# MicroSpecSensorBoard_periphericDevices_V.net
KiCad netlist of a schematic drawn in Altium Designer
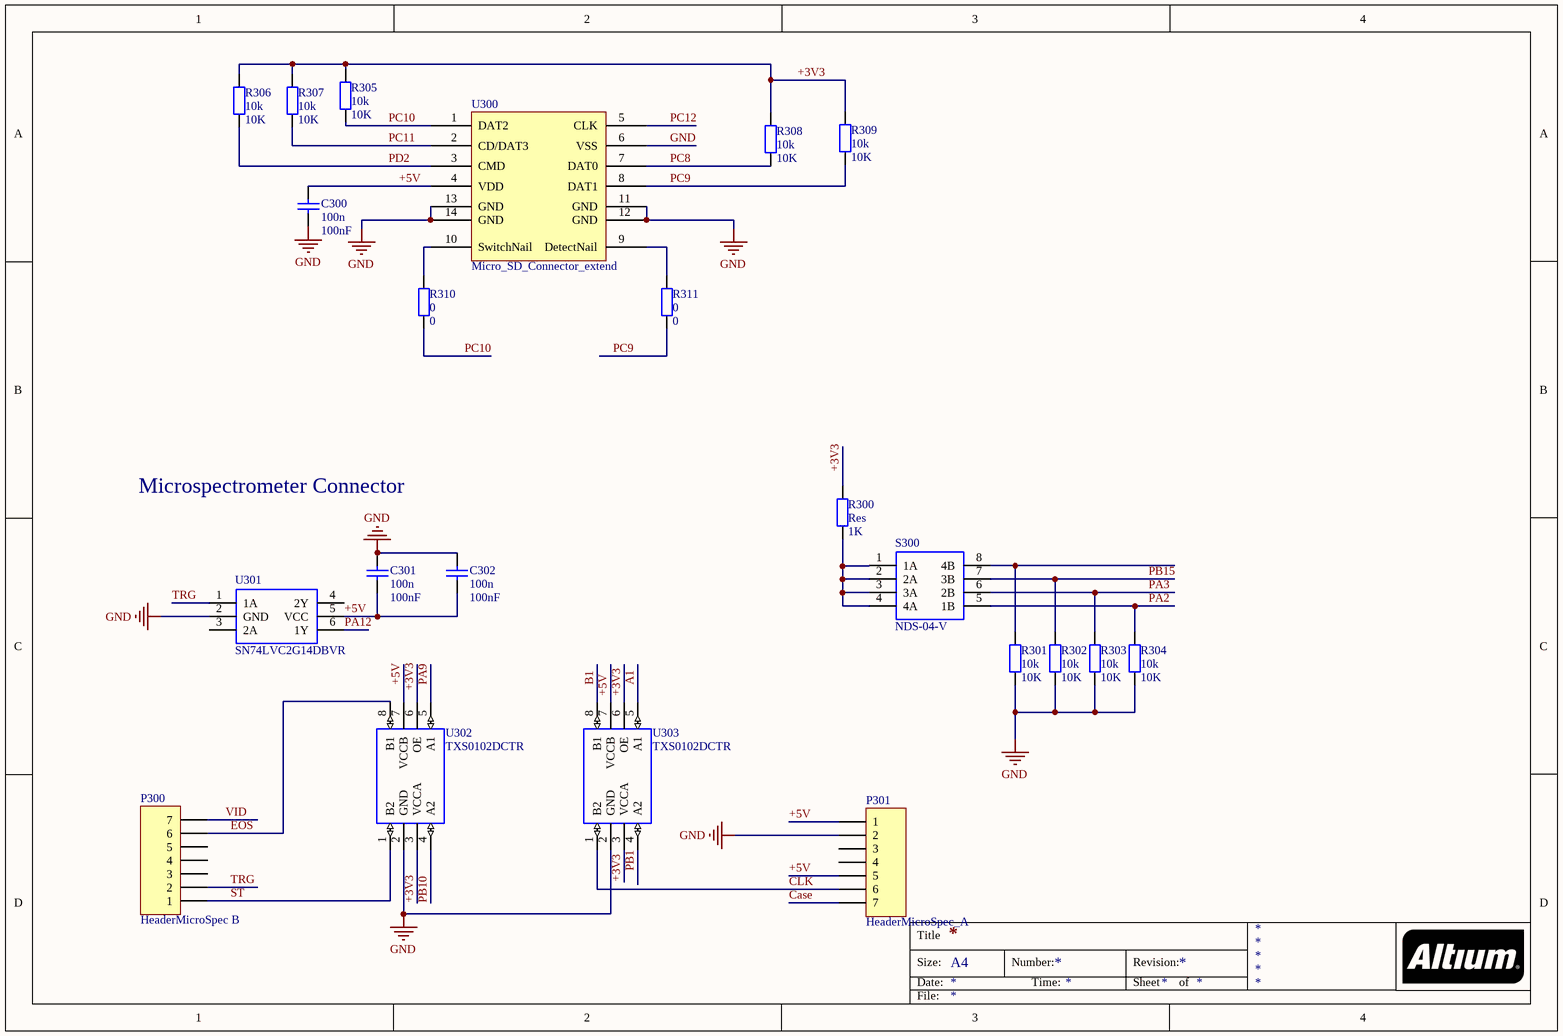
[diagram p0: MicroSpecSensorBoard_periphericDevices_V2_1.SchDoc]

(export (version "E")
  (design (tool "Eeschema 10.0.6"))
  (components
    (comp (ref "C300")
      (value "100n")
      (footprint "6-0805_L")
      (description "Capacitor")
      (fields (field (name "ALTIUM_VALUE") "100nF") (field (name "PUBLISHER") "Altium Limited"))
      (libsource (lib "USER_Library") (part "Cap"))
    )
    (comp (ref "C301")
      (value "100n")
      (footprint "6-0805_L")
      (description "Capacitor")
      (fields (field (name "ALTIUM_VALUE") "100nF") (field (name "PUBLISHER") "Altium Limited"))
      (libsource (lib "USER_Library") (part "Cap"))
    )
    (comp (ref "C302")
      (value "100n")
      (footprint "6-0805_L")
      (description "Capacitor")
      (fields (field (name "ALTIUM_VALUE") "100nF") (field (name "PUBLISHER") "Altium Limited"))
      (libsource (lib "USER_Library") (part "Cap"))
    )
    (comp (ref "P300")
      (value "HeaderMicroSpec B")
      (footprint "HDR1X7")
      (description "Header, 7-Pin")
      (fields (field (name "PUBLISHER") "Altium Limited"))
      (libsource (lib "Miscellaneous Connectors") (part "Header 7"))
    )
    (comp (ref "P301")
      (value "HeaderMicroSpec_A")
      (footprint "HDR1X7")
      (description "Header, 7-Pin")
      (fields (field (name "PUBLISHER") "Altium Limited"))
      (libsource (lib "") (part "Header 7_1"))
    )
    (comp (ref "R300")
      (value "Res")
      (footprint "6-0805_L")
      (description "Resistor")
      (fields (field (name "ALTIUM_VALUE") "1K") (field (name "PUBLISHER") "Altium Limited"))
      (libsource (lib "USER_Library") (part "Res2"))
    )
    (comp (ref "R301")
      (value "10k")
      (footprint "6-0805_L")
      (description "Resistor")
      (fields (field (name "ALTIUM_VALUE") "10K") (field (name "PUBLISHER") "Altium Limited"))
      (libsource (lib "USER_Library") (part "Res2"))
    )
    (comp (ref "R302")
      (value "10k")
      (footprint "6-0805_L")
      (description "Resistor")
      (fields (field (name "ALTIUM_VALUE") "10K") (field (name "PUBLISHER") "Altium Limited"))
      (libsource (lib "USER_Library") (part "Res2"))
    )
    (comp (ref "R303")
      (value "10k")
      (footprint "6-0805_L")
      (description "Resistor")
      (fields (field (name "ALTIUM_VALUE") "10K") (field (name "PUBLISHER") "Altium Limited"))
      (libsource (lib "USER_Library") (part "Res2"))
    )
    (comp (ref "R304")
      (value "10k")
      (footprint "6-0805_L")
      (description "Resistor")
      (fields (field (name "ALTIUM_VALUE") "10K") (field (name "PUBLISHER") "Altium Limited"))
      (libsource (lib "USER_Library") (part "Res2"))
    )
    (comp (ref "R305")
      (value "10k")
      (footprint "6-0805_L")
      (description "Resistor")
      (fields (field (name "ALTIUM_VALUE") "10K") (field (name "PUBLISHER") "Altium Limited"))
      (libsource (lib "USER_Library") (part "Res2"))
    )
    (comp (ref "R306")
      (value "10k")
      (footprint "6-0805_L")
      (description "Resistor")
      (fields (field (name "ALTIUM_VALUE") "10K") (field (name "PUBLISHER") "Altium Limited"))
      (libsource (lib "USER_Library") (part "Res2"))
    )
    (comp (ref "R307")
      (value "10k")
      (footprint "6-0805_L")
      (description "Resistor")
      (fields (field (name "ALTIUM_VALUE") "10K") (field (name "PUBLISHER") "Altium Limited"))
      (libsource (lib "USER_Library") (part "Res2"))
    )
    (comp (ref "R308")
      (value "10k")
      (footprint "6-0805_L")
      (description "Resistor")
      (fields (field (name "ALTIUM_VALUE") "10K") (field (name "PUBLISHER") "Altium Limited"))
      (libsource (lib "") (part "Res2_1"))
    )
    (comp (ref "R309")
      (value "10k")
      (footprint "6-0805_L")
      (description "Resistor")
      (fields (field (name "ALTIUM_VALUE") "10K") (field (name "PUBLISHER") "Altium Limited"))
      (libsource (lib "USER_Library") (part "Res2"))
    )
    (comp (ref "R310")
      (value "0")
      (footprint "6-0805_L")
      (description "Resistor")
      (fields (field (name "ALTIUM_VALUE") "0") (field (name "PUBLISHER") "Altium Limited"))
      (libsource (lib "USER_Library") (part "Res2"))
    )
    (comp (ref "R311")
      (value "0")
      (footprint "6-0805_L")
      (description "Resistor")
      (fields (field (name "ALTIUM_VALUE") "0") (field (name "PUBLISHER") "Altium Limited"))
      (libsource (lib "USER_Library") (part "Res2"))
    )
    (comp (ref "S300")
      (value "NDS-04-V")
      (footprint "DIPS762W60P254L1152H705Q8N")
      (description "Switch DIP 4 pos raised act solder 4 Way Through Hole DIP Switch SPST, Raised Actuator")
      (fields (field (name "RS PART NUMBER") "8772126"))
      (libsource (lib "USER_Library") (part "NDS-04-V"))
    )
    (comp (ref "U300")
      (value "Micro_SD_Connector_extend")
      (footprint "MICRO-SD-CON-EXT")
      (libsource (lib "USER_Library") (part "Micro_SD_Connector_extend"))
    )
    (comp (ref "U301")
      (value "SN74LVC2G14DBVR")
      (footprint "SOT95P280X145-6N")
      (description "DUAL SCHMITT-TRIGGER INVERTER")
      (fields (field (name "RS PART NUMBER") "6628926P"))
      (libsource (lib "USER_Library") (part "SN74LVC2G14DBVR"))
    )
    (comp (ref "U302")
      (value "TXS0102DCTR")
      (footprint "SOP65P400X130-8N")
      (description "2-Bit Bidirectional Voltage-Level Shifter for Open-Drain and Push-Pull Application")
      (fields (field (name "RS PART NUMBER") "1628462"))
      (libsource (lib "USER_Library") (part "TXS0102DCTR"))
    )
    (comp (ref "U303")
      (value "TXS0102DCTR")
      (footprint "SOP65P400X130-8N")
      (description "2-Bit Bidirectional Voltage-Level Shifter for Open-Drain and Push-Pull Application")
      (fields (field (name "RS PART NUMBER") "1628462"))
      (libsource (lib "USER_Library") (part "TXS0102DCTR"))
    )
  )
  (nets
    (net (code "1") (name "/+3V3") (class "Default")
      (node (ref "R300") (pin "2") (pinfunction "2_2") (pintype "passive"))
      (node (ref "R305") (pin "2") (pinfunction "2_2") (pintype "passive"))
      (node (ref "R306") (pin "2") (pinfunction "2_2") (pintype "passive"))
      (node (ref "R307") (pin "2") (pinfunction "2_2") (pintype "passive"))
      (node (ref "R308") (pin "1") (pinfunction "1_1") (pintype "passive"))
      (node (ref "R309") (pin "2") (pinfunction "2_2") (pintype "passive"))
      (node (ref "U302") (pin "3") (pinfunction "VCCA_3") (pintype "power_in"))
      (node (ref "U302") (pin "6") (pinfunction "OE_6") (pintype "passive"))
      (node (ref "U303") (pin "3") (pinfunction "VCCA_3") (pintype "power_in"))
      (node (ref "U303") (pin "6") (pinfunction "OE_6") (pintype "passive"))
    )
    (net (code "2") (name "/+5V") (class "Default")
      (node (ref "C300") (pin "1") (pinfunction "1_1") (pintype "passive"))
      (node (ref "C301") (pin "2") (pinfunction "2_2") (pintype "passive"))
      (node (ref "C302") (pin "2") (pinfunction "2_2") (pintype "passive"))
      (node (ref "P301") (pin "1") (pinfunction "1_1") (pintype "passive"))
      (node (ref "P301") (pin "5") (pinfunction "5_5") (pintype "passive"))
      (node (ref "U300") (pin "4") (pinfunction "VDD_4") (pintype "passive"))
      (node (ref "U301") (pin "5") (pinfunction "VCC_5") (pintype "passive"))
      (node (ref "U302") (pin "7") (pinfunction "VCCB_7") (pintype "power_in"))
      (node (ref "U303") (pin "7") (pinfunction "VCCB_7") (pintype "power_in"))
    )
    (net (code "3") (name "/A1") (class "Default")
      (node (ref "U303") (pin "5") (pinfunction "A1_5") (pintype "bidirectional"))
    )
    (net (code "4") (name "/B1") (class "Default")
      (node (ref "U303") (pin "8") (pinfunction "B1_8") (pintype "bidirectional"))
    )
    (net (code "5") (name "/CLK") (class "Default")
      (node (ref "P301") (pin "6") (pinfunction "6_6") (pintype "passive"))
      (node (ref "U303") (pin "1") (pinfunction "B2_1") (pintype "bidirectional"))
    )
    (net (code "6") (name "/Case") (class "Default")
      (node (ref "P301") (pin "7") (pinfunction "7_7") (pintype "passive"))
    )
    (net (code "7") (name "/EOS") (class "Default")
      (node (ref "P300") (pin "6") (pinfunction "6_6") (pintype "passive"))
      (node (ref "U302") (pin "8") (pinfunction "B1_8") (pintype "bidirectional"))
    )
    (net (code "8") (name "/PA2") (class "Default")
      (node (ref "R304") (pin "2") (pinfunction "2_2") (pintype "passive"))
      (node (ref "S300") (pin "5") (pinfunction "1B_5") (pintype "passive"))
    )
    (net (code "9") (name "/PA3") (class "Default")
      (node (ref "R303") (pin "2") (pinfunction "2_2") (pintype "passive"))
      (node (ref "S300") (pin "6") (pinfunction "2B_6") (pintype "passive"))
    )
    (net (code "10") (name "/PA9") (class "Default")
      (node (ref "U302") (pin "5") (pinfunction "A1_5") (pintype "bidirectional"))
    )
    (net (code "11") (name "/PA12") (class "Default")
      (node (ref "U301") (pin "6") (pinfunction "1Y_6") (pintype "passive"))
    )
    (net (code "12") (name "/PB1") (class "Default")
      (node (ref "U303") (pin "4") (pinfunction "A2_4") (pintype "bidirectional"))
    )
    (net (code "13") (name "/PB10") (class "Default")
      (node (ref "U302") (pin "4") (pinfunction "A2_4") (pintype "bidirectional"))
    )
    (net (code "14") (name "/PB15") (class "Default")
      (node (ref "R302") (pin "2") (pinfunction "2_2") (pintype "passive"))
      (node (ref "S300") (pin "7") (pinfunction "3B_7") (pintype "passive"))
    )
    (net (code "15") (name "/PC8") (class "Default")
      (node (ref "R308") (pin "2") (pinfunction "2_2") (pintype "passive"))
      (node (ref "U300") (pin "7") (pinfunction "DAT0_7") (pintype "passive"))
    )
    (net (code "16") (name "/PC9") (class "Default")
      (node (ref "R309") (pin "1") (pinfunction "1_1") (pintype "passive"))
      (node (ref "R311") (pin "1") (pinfunction "1_1") (pintype "passive"))
      (node (ref "U300") (pin "8") (pinfunction "DAT1_8") (pintype "passive"))
    )
    (net (code "17") (name "/PC10") (class "Default")
      (node (ref "R305") (pin "1") (pinfunction "1_1") (pintype "passive"))
      (node (ref "R310") (pin "1") (pinfunction "1_1") (pintype "passive"))
      (node (ref "U300") (pin "1") (pinfunction "DAT2_1") (pintype "passive"))
    )
    (net (code "18") (name "/PC11") (class "Default")
      (node (ref "R307") (pin "1") (pinfunction "1_1") (pintype "passive"))
      (node (ref "U300") (pin "2") (pinfunction "CD/DAT3_2") (pintype "passive"))
    )
    (net (code "19") (name "/PC12") (class "Default")
      (node (ref "U300") (pin "5") (pinfunction "CLK_5") (pintype "passive"))
    )
    (net (code "20") (name "/PD2") (class "Default")
      (node (ref "R306") (pin "1") (pinfunction "1_1") (pintype "passive"))
      (node (ref "U300") (pin "3") (pinfunction "CMD_3") (pintype "passive"))
    )
    (net (code "21") (name "/ST") (class "Default")
      (node (ref "P300") (pin "1") (pinfunction "1_1") (pintype "passive"))
      (node (ref "U302") (pin "1") (pinfunction "B2_1") (pintype "bidirectional"))
    )
    (net (code "22") (name "/TRG") (class "Default")
      (node (ref "P300") (pin "2") (pinfunction "2_2") (pintype "passive"))
      (node (ref "U301") (pin "1") (pinfunction "1A_1") (pintype "passive"))
    )
    (net (code "23") (name "/VID") (class "Default")
      (node (ref "P300") (pin "7") (pinfunction "7_7") (pintype "passive"))
    )
    (net (code "24") (name "GND") (class "Default")
      (node (ref "C300") (pin "2") (pinfunction "2_2") (pintype "passive"))
      (node (ref "C301") (pin "1") (pinfunction "1_1") (pintype "passive"))
      (node (ref "C302") (pin "1") (pinfunction "1_1") (pintype "passive"))
      (node (ref "P301") (pin "2") (pinfunction "2_2") (pintype "passive"))
      (node (ref "R301") (pin "1") (pinfunction "1_1") (pintype "passive"))
      (node (ref "R302") (pin "1") (pinfunction "1_1") (pintype "passive"))
      (node (ref "R303") (pin "1") (pinfunction "1_1") (pintype "passive"))
      (node (ref "R304") (pin "1") (pinfunction "1_1") (pintype "passive"))
      (node (ref "U300") (pin "11") (pinfunction "GND_11") (pintype "power_in"))
      (node (ref "U300") (pin "12") (pinfunction "GND_12") (pintype "power_in"))
      (node (ref "U300") (pin "13") (pinfunction "GND_13") (pintype "power_in"))
      (node (ref "U300") (pin "14") (pinfunction "GND_14") (pintype "power_in"))
      (node (ref "U300") (pin "6") (pinfunction "VSS_6") (pintype "passive"))
      (node (ref "U301") (pin "2") (pinfunction "GND_2") (pintype "passive"))
      (node (ref "U302") (pin "2") (pinfunction "GND_2") (pintype "passive"))
      (node (ref "U303") (pin "2") (pinfunction "GND_2") (pintype "passive"))
    )
    (net (code "25") (name "Net-(S300-1A)") (class "Default")
      (node (ref "R300") (pin "1") (pinfunction "1_1") (pintype "passive"))
      (node (ref "S300") (pin "1") (pinfunction "1A_1") (pintype "passive"))
      (node (ref "S300") (pin "2") (pinfunction "2A_2") (pintype "passive"))
      (node (ref "S300") (pin "3") (pinfunction "3A_3") (pintype "passive"))
      (node (ref "S300") (pin "4") (pinfunction "4A_4") (pintype "passive"))
    )
    (net (code "26") (name "Net-(S300-4B)") (class "Default")
      (node (ref "R301") (pin "2") (pinfunction "2_2") (pintype "passive"))
      (node (ref "S300") (pin "8") (pinfunction "4B_8") (pintype "passive"))
    )
    (net (code "27") (name "Net-(U300-DetectNail)") (class "Default")
      (node (ref "R311") (pin "2") (pinfunction "2_2") (pintype "passive"))
      (node (ref "U300") (pin "9") (pinfunction "DetectNail_9") (pintype "passive"))
    )
    (net (code "28") (name "Net-(U300-SwitchNail)") (class "Default")
      (node (ref "R310") (pin "2") (pinfunction "2_2") (pintype "passive"))
      (node (ref "U300") (pin "10") (pinfunction "SwitchNail_10") (pintype "passive"))
    )
    (net (code "29") (name "unconnected-(P300-Pad3)") (class "Default")
      (node (ref "P300") (pin "3") (pinfunction "3_3") (pintype "passive"))
    )
    (net (code "30") (name "unconnected-(P300-Pad4)") (class "Default")
      (node (ref "P300") (pin "4") (pinfunction "4_4") (pintype "passive"))
    )
    (net (code "31") (name "unconnected-(P300-Pad5)") (class "Default")
      (node (ref "P300") (pin "5") (pinfunction "5_5") (pintype "passive"))
    )
    (net (code "32") (name "unconnected-(P301-Pad3)") (class "Default")
      (node (ref "P301") (pin "3") (pinfunction "3_3") (pintype "passive"))
    )
    (net (code "33") (name "unconnected-(P301-Pad4)") (class "Default")
      (node (ref "P301") (pin "4") (pinfunction "4_4") (pintype "passive"))
    )
    (net (code "34") (name "unconnected-(U301-2A-Pad3)") (class "Default")
      (node (ref "U301") (pin "3") (pinfunction "2A_3") (pintype "passive"))
    )
    (net (code "35") (name "unconnected-(U301-2Y-Pad4)") (class "Default")
      (node (ref "U301") (pin "4") (pinfunction "2Y_4") (pintype "passive"))
    )
  )
)
